# Shift_register.net
KiCad netlist of a schematic drawn in Altium Designer
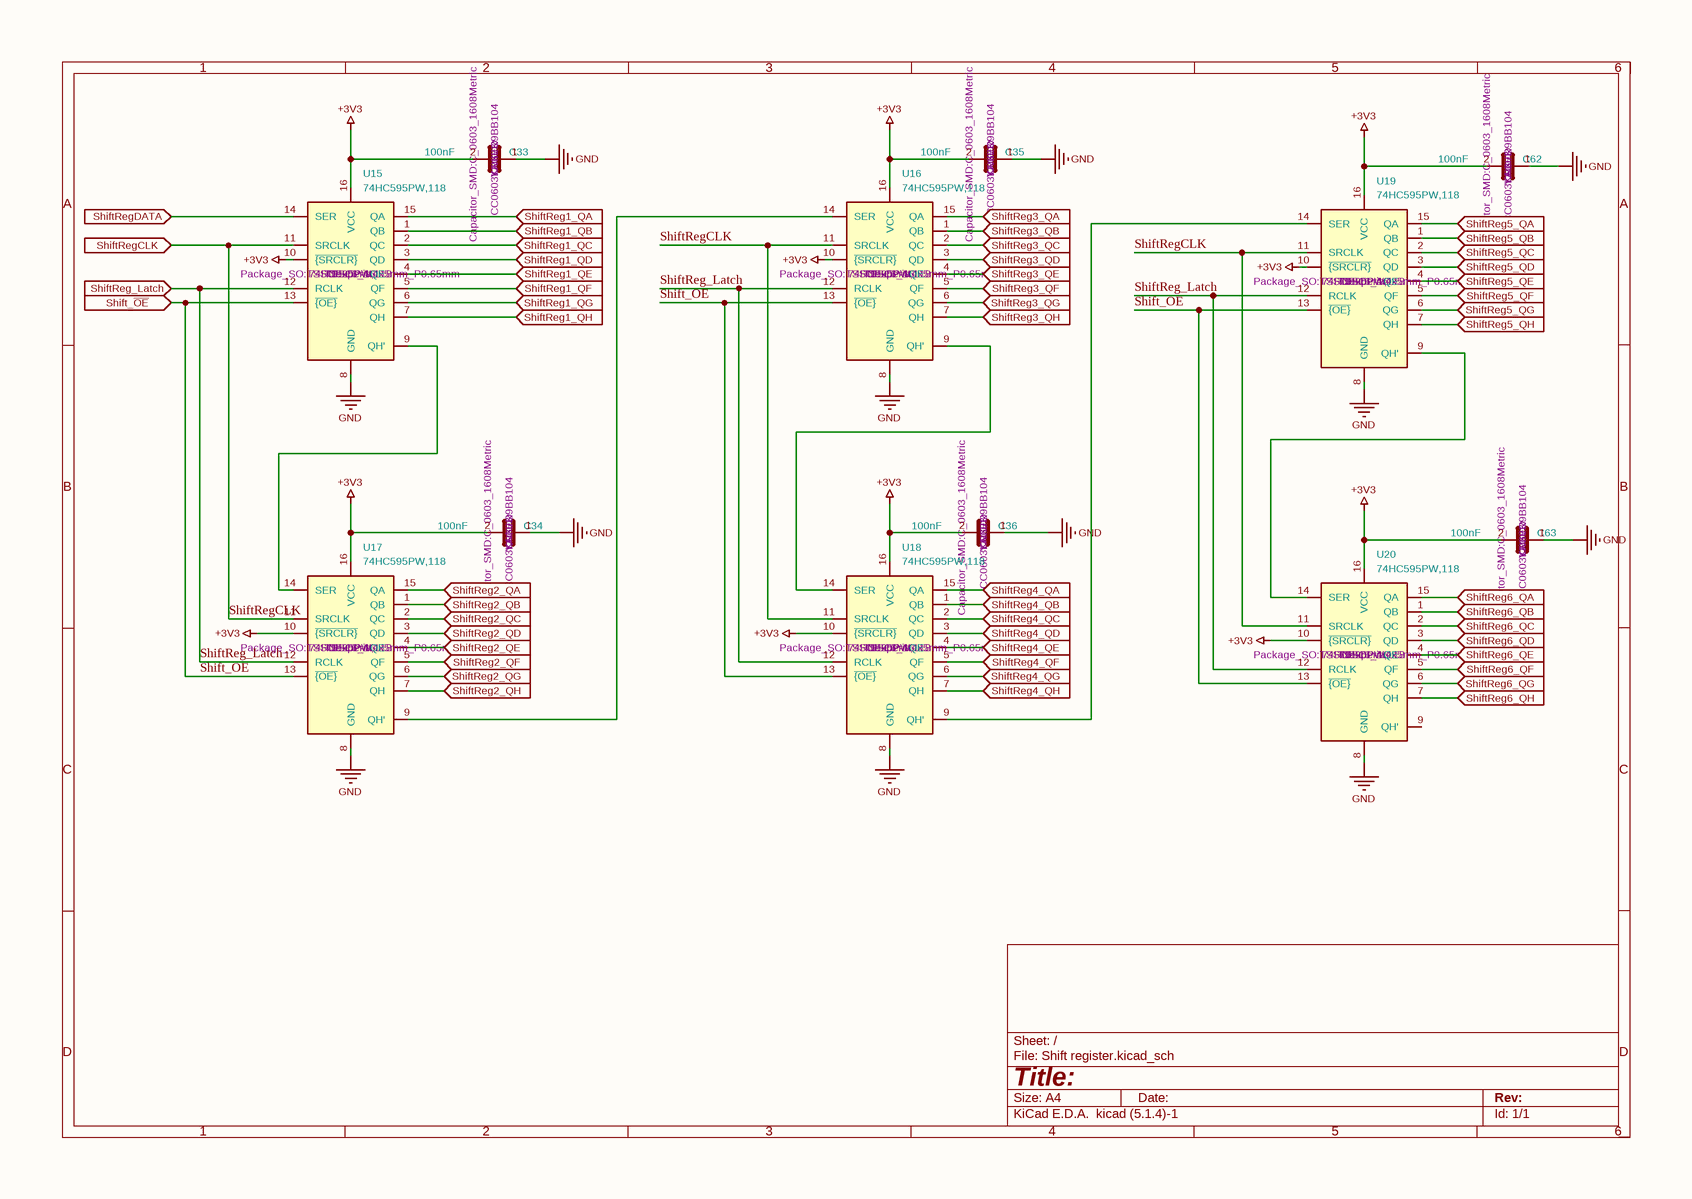
[diagram p0: Shift register.SchDoc]

(export (version "E")
  (design (tool "Eeschema 10.0.6"))
  (components
    (comp (ref "C33")
      (value "100nF")
      (footprint "Capacitor_SMD:C_0603_1608Metric")
      (fields
        (field (name "MANUFACTURER PART NUMBER") "CC0603KRX7R9BB104")
        (field (name "MANUFACTURER") "YAGEO")
        (field (name "PACKAGE") "C0603")
      )
      (libsource (lib "Device") (part "C"))
    )
    (comp (ref "C34")
      (value "100nF")
      (footprint "Capacitor_SMD:C_0603_1608Metric")
      (fields
        (field (name "MANUFACTURER PART NUMBER") "CC0603KRX7R9BB104")
        (field (name "MANUFACTURER") "YAGEO")
        (field (name "PACKAGE") "C0603")
      )
      (libsource (lib "Device") (part "C"))
    )
    (comp (ref "C35")
      (value "100nF")
      (footprint "Capacitor_SMD:C_0603_1608Metric")
      (fields
        (field (name "MANUFACTURER PART NUMBER") "CC0603KRX7R9BB104")
        (field (name "MANUFACTURER") "YAGEO")
        (field (name "PACKAGE") "C0603")
      )
      (libsource (lib "Device") (part "C"))
    )
    (comp (ref "C36")
      (value "100nF")
      (footprint "Capacitor_SMD:C_0603_1608Metric")
      (fields
        (field (name "MANUFACTURER PART NUMBER") "CC0603KRX7R9BB104")
        (field (name "MANUFACTURER") "YAGEO")
        (field (name "PACKAGE") "C0603")
      )
      (libsource (lib "Device") (part "C"))
    )
    (comp (ref "C62")
      (value "100nF")
      (footprint "Capacitor_SMD:C_0603_1608Metric")
      (fields
        (field (name "MANUFACTURER PART NUMBER") "CC0603KRX7R9BB104")
        (field (name "MANUFACTURER") "YAGEO")
        (field (name "PACKAGE") "C0603")
      )
      (libsource (lib "Device") (part "C"))
    )
    (comp (ref "C63")
      (value "100nF")
      (footprint "Capacitor_SMD:C_0603_1608Metric")
      (fields
        (field (name "MANUFACTURER PART NUMBER") "CC0603KRX7R9BB104")
        (field (name "MANUFACTURER") "YAGEO")
        (field (name "PACKAGE") "C0603")
      )
      (libsource (lib "Device") (part "C"))
    )
    (comp (ref "U15")
      (value "74HC595PW,118")
      (footprint "Package_SO:TSSOP-16_4.4x5mm_P0.65mm")
      (fields
        (field (name "MANUFACTURER PART NUMBER") "74HC595PW,118")
        (field (name "MANUFACTURER") "Nexperia")
        (field (name "PACKAGE") "TSSOP-16")
      )
      (libsource (lib "74xx") (part "74HC595"))
    )
    (comp (ref "U16")
      (value "74HC595PW,118")
      (footprint "Package_SO:TSSOP-16_4.4x5mm_P0.65mm")
      (fields
        (field (name "MANUFACTURER PART NUMBER") "74HC595PW,118")
        (field (name "MANUFACTURER") "Nexperia")
        (field (name "PACKAGE") "TSSOP-16")
      )
      (libsource (lib "74xx") (part "74HC595"))
    )
    (comp (ref "U17")
      (value "74HC595PW,118")
      (footprint "Package_SO:TSSOP-16_4.4x5mm_P0.65mm")
      (fields
        (field (name "MANUFACTURER PART NUMBER") "74HC595PW,118")
        (field (name "MANUFACTURER") "Nexperia")
        (field (name "PACKAGE") "TSSOP-16")
      )
      (libsource (lib "74xx") (part "74HC595"))
    )
    (comp (ref "U18")
      (value "74HC595PW,118")
      (footprint "Package_SO:TSSOP-16_4.4x5mm_P0.65mm")
      (fields
        (field (name "MANUFACTURER PART NUMBER") "74HC595PW,118")
        (field (name "MANUFACTURER") "Nexperia")
        (field (name "PACKAGE") "TSSOP-16")
      )
      (libsource (lib "74xx") (part "74HC595"))
    )
    (comp (ref "U19")
      (value "74HC595PW,118")
      (footprint "Package_SO:TSSOP-16_4.4x5mm_P0.65mm")
      (fields
        (field (name "MANUFACTURER PART NUMBER") "74HC595PW,118")
        (field (name "MANUFACTURER") "Nexperia")
        (field (name "PACKAGE") "TSSOP-16")
      )
      (libsource (lib "74xx") (part "74HC595"))
    )
    (comp (ref "U20")
      (value "74HC595PW,118")
      (footprint "Package_SO:TSSOP-16_4.4x5mm_P0.65mm")
      (fields
        (field (name "MANUFACTURER PART NUMBER") "74HC595PW,118")
        (field (name "MANUFACTURER") "Nexperia")
        (field (name "PACKAGE") "TSSOP-16")
      )
      (libsource (lib "74xx") (part "74HC595"))
    )
  )
  (nets
    (net (code "1") (name "+3V3") (class "Default")
      (node (ref "C33") (pin "2") (pinfunction "2_2") (pintype "passive"))
      (node (ref "C34") (pin "2") (pinfunction "2_2") (pintype "passive"))
      (node (ref "C35") (pin "2") (pinfunction "2_2") (pintype "passive"))
      (node (ref "C36") (pin "2") (pinfunction "2_2") (pintype "passive"))
      (node (ref "C62") (pin "2") (pinfunction "2_2") (pintype "passive"))
      (node (ref "C63") (pin "2") (pinfunction "2_2") (pintype "passive"))
      (node (ref "U15") (pin "10") (pinfunction "~{{SRCLR}}_10") (pintype "passive"))
      (node (ref "U15") (pin "16") (pinfunction "VCC_16") (pintype "passive"))
      (node (ref "U16") (pin "10") (pinfunction "~{{SRCLR}}_10") (pintype "passive"))
      (node (ref "U16") (pin "16") (pinfunction "VCC_16") (pintype "passive"))
      (node (ref "U17") (pin "10") (pinfunction "~{{SRCLR}}_10") (pintype "passive"))
      (node (ref "U17") (pin "16") (pinfunction "VCC_16") (pintype "passive"))
      (node (ref "U18") (pin "10") (pinfunction "~{{SRCLR}}_10") (pintype "passive"))
      (node (ref "U18") (pin "16") (pinfunction "VCC_16") (pintype "passive"))
      (node (ref "U19") (pin "10") (pinfunction "~{{SRCLR}}_10") (pintype "passive"))
      (node (ref "U19") (pin "16") (pinfunction "VCC_16") (pintype "passive"))
      (node (ref "U20") (pin "10") (pinfunction "~{{SRCLR}}_10") (pintype "passive"))
      (node (ref "U20") (pin "16") (pinfunction "VCC_16") (pintype "passive"))
    )
    (net (code "2") (name "/ShiftReg1_QA") (class "Default")
      (node (ref "U15") (pin "15") (pinfunction "QA_15") (pintype "passive"))
    )
    (net (code "3") (name "/ShiftReg1_QB") (class "Default")
      (node (ref "U15") (pin "1") (pinfunction "QB_1") (pintype "passive"))
    )
    (net (code "4") (name "/ShiftReg1_QC") (class "Default")
      (node (ref "U15") (pin "2") (pinfunction "QC_2") (pintype "passive"))
    )
    (net (code "5") (name "/ShiftReg1_QD") (class "Default")
      (node (ref "U15") (pin "3") (pinfunction "QD_3") (pintype "passive"))
    )
    (net (code "6") (name "/ShiftReg1_QE") (class "Default")
      (node (ref "U15") (pin "4") (pinfunction "QE_4") (pintype "passive"))
    )
    (net (code "7") (name "/ShiftReg1_QF") (class "Default")
      (node (ref "U15") (pin "5") (pinfunction "QF_5") (pintype "passive"))
    )
    (net (code "8") (name "/ShiftReg1_QG") (class "Default")
      (node (ref "U15") (pin "6") (pinfunction "QG_6") (pintype "passive"))
    )
    (net (code "9") (name "/ShiftReg1_QH") (class "Default")
      (node (ref "U15") (pin "7") (pinfunction "QH_7") (pintype "passive"))
    )
    (net (code "10") (name "/ShiftReg2_QA") (class "Default")
      (node (ref "U17") (pin "15") (pinfunction "QA_15") (pintype "passive"))
    )
    (net (code "11") (name "/ShiftReg2_QB") (class "Default")
      (node (ref "U17") (pin "1") (pinfunction "QB_1") (pintype "passive"))
    )
    (net (code "12") (name "/ShiftReg2_QC") (class "Default")
      (node (ref "U17") (pin "2") (pinfunction "QC_2") (pintype "passive"))
    )
    (net (code "13") (name "/ShiftReg2_QD") (class "Default")
      (node (ref "U17") (pin "3") (pinfunction "QD_3") (pintype "passive"))
    )
    (net (code "14") (name "/ShiftReg2_QE") (class "Default")
      (node (ref "U17") (pin "4") (pinfunction "QE_4") (pintype "passive"))
    )
    (net (code "15") (name "/ShiftReg2_QF") (class "Default")
      (node (ref "U17") (pin "5") (pinfunction "QF_5") (pintype "passive"))
    )
    (net (code "16") (name "/ShiftReg2_QG") (class "Default")
      (node (ref "U17") (pin "6") (pinfunction "QG_6") (pintype "passive"))
    )
    (net (code "17") (name "/ShiftReg2_QH") (class "Default")
      (node (ref "U17") (pin "7") (pinfunction "QH_7") (pintype "passive"))
    )
    (net (code "18") (name "/ShiftReg3_QA") (class "Default")
      (node (ref "U16") (pin "15") (pinfunction "QA_15") (pintype "passive"))
    )
    (net (code "19") (name "/ShiftReg3_QB") (class "Default")
      (node (ref "U16") (pin "1") (pinfunction "QB_1") (pintype "passive"))
    )
    (net (code "20") (name "/ShiftReg3_QC") (class "Default")
      (node (ref "U16") (pin "2") (pinfunction "QC_2") (pintype "passive"))
    )
    (net (code "21") (name "/ShiftReg3_QD") (class "Default")
      (node (ref "U16") (pin "3") (pinfunction "QD_3") (pintype "passive"))
    )
    (net (code "22") (name "/ShiftReg3_QE") (class "Default")
      (node (ref "U16") (pin "4") (pinfunction "QE_4") (pintype "passive"))
    )
    (net (code "23") (name "/ShiftReg3_QF") (class "Default")
      (node (ref "U16") (pin "5") (pinfunction "QF_5") (pintype "passive"))
    )
    (net (code "24") (name "/ShiftReg3_QG") (class "Default")
      (node (ref "U16") (pin "6") (pinfunction "QG_6") (pintype "passive"))
    )
    (net (code "25") (name "/ShiftReg3_QH") (class "Default")
      (node (ref "U16") (pin "7") (pinfunction "QH_7") (pintype "passive"))
    )
    (net (code "26") (name "/ShiftReg4_QA") (class "Default")
      (node (ref "U18") (pin "15") (pinfunction "QA_15") (pintype "passive"))
    )
    (net (code "27") (name "/ShiftReg4_QB") (class "Default")
      (node (ref "U18") (pin "1") (pinfunction "QB_1") (pintype "passive"))
    )
    (net (code "28") (name "/ShiftReg4_QC") (class "Default")
      (node (ref "U18") (pin "2") (pinfunction "QC_2") (pintype "passive"))
    )
    (net (code "29") (name "/ShiftReg4_QD") (class "Default")
      (node (ref "U18") (pin "3") (pinfunction "QD_3") (pintype "passive"))
    )
    (net (code "30") (name "/ShiftReg4_QE") (class "Default")
      (node (ref "U18") (pin "4") (pinfunction "QE_4") (pintype "passive"))
    )
    (net (code "31") (name "/ShiftReg4_QF") (class "Default")
      (node (ref "U18") (pin "5") (pinfunction "QF_5") (pintype "passive"))
    )
    (net (code "32") (name "/ShiftReg4_QG") (class "Default")
      (node (ref "U18") (pin "6") (pinfunction "QG_6") (pintype "passive"))
    )
    (net (code "33") (name "/ShiftReg4_QH") (class "Default")
      (node (ref "U18") (pin "7") (pinfunction "QH_7") (pintype "passive"))
    )
    (net (code "34") (name "/ShiftReg5_QA") (class "Default")
      (node (ref "U19") (pin "15") (pinfunction "QA_15") (pintype "passive"))
    )
    (net (code "35") (name "/ShiftReg5_QB") (class "Default")
      (node (ref "U19") (pin "1") (pinfunction "QB_1") (pintype "passive"))
    )
    (net (code "36") (name "/ShiftReg5_QC") (class "Default")
      (node (ref "U19") (pin "2") (pinfunction "QC_2") (pintype "passive"))
    )
    (net (code "37") (name "/ShiftReg5_QD") (class "Default")
      (node (ref "U19") (pin "3") (pinfunction "QD_3") (pintype "passive"))
    )
    (net (code "38") (name "/ShiftReg5_QE") (class "Default")
      (node (ref "U19") (pin "4") (pinfunction "QE_4") (pintype "passive"))
    )
    (net (code "39") (name "/ShiftReg5_QF") (class "Default")
      (node (ref "U19") (pin "5") (pinfunction "QF_5") (pintype "passive"))
    )
    (net (code "40") (name "/ShiftReg5_QG") (class "Default")
      (node (ref "U19") (pin "6") (pinfunction "QG_6") (pintype "passive"))
    )
    (net (code "41") (name "/ShiftReg5_QH") (class "Default")
      (node (ref "U19") (pin "7") (pinfunction "QH_7") (pintype "passive"))
    )
    (net (code "42") (name "/ShiftReg6_QA") (class "Default")
      (node (ref "U20") (pin "15") (pinfunction "QA_15") (pintype "passive"))
    )
    (net (code "43") (name "/ShiftReg6_QB") (class "Default")
      (node (ref "U20") (pin "1") (pinfunction "QB_1") (pintype "passive"))
    )
    (net (code "44") (name "/ShiftReg6_QC") (class "Default")
      (node (ref "U20") (pin "2") (pinfunction "QC_2") (pintype "passive"))
    )
    (net (code "45") (name "/ShiftReg6_QD") (class "Default")
      (node (ref "U20") (pin "3") (pinfunction "QD_3") (pintype "passive"))
    )
    (net (code "46") (name "/ShiftReg6_QE") (class "Default")
      (node (ref "U20") (pin "4") (pinfunction "QE_4") (pintype "passive"))
    )
    (net (code "47") (name "/ShiftReg6_QF") (class "Default")
      (node (ref "U20") (pin "5") (pinfunction "QF_5") (pintype "passive"))
    )
    (net (code "48") (name "/ShiftReg6_QG") (class "Default")
      (node (ref "U20") (pin "6") (pinfunction "QG_6") (pintype "passive"))
    )
    (net (code "49") (name "/ShiftReg6_QH") (class "Default")
      (node (ref "U20") (pin "7") (pinfunction "QH_7") (pintype "passive"))
    )
    (net (code "50") (name "/ShiftRegCLK") (class "Default")
      (node (ref "U15") (pin "11") (pinfunction "SRCLK_11") (pintype "passive"))
      (node (ref "U16") (pin "11") (pinfunction "SRCLK_11") (pintype "passive"))
      (node (ref "U17") (pin "11") (pinfunction "SRCLK_11") (pintype "passive"))
      (node (ref "U18") (pin "11") (pinfunction "SRCLK_11") (pintype "passive"))
      (node (ref "U19") (pin "11") (pinfunction "SRCLK_11") (pintype "passive"))
      (node (ref "U20") (pin "11") (pinfunction "SRCLK_11") (pintype "passive"))
    )
    (net (code "51") (name "/ShiftRegDATA") (class "Default")
      (node (ref "U15") (pin "14") (pinfunction "SER_14") (pintype "passive"))
    )
    (net (code "52") (name "/ShiftReg_Latch") (class "Default")
      (node (ref "U15") (pin "12") (pinfunction "RCLK_12") (pintype "passive"))
      (node (ref "U16") (pin "12") (pinfunction "RCLK_12") (pintype "passive"))
      (node (ref "U17") (pin "12") (pinfunction "RCLK_12") (pintype "passive"))
      (node (ref "U18") (pin "12") (pinfunction "RCLK_12") (pintype "passive"))
      (node (ref "U19") (pin "12") (pinfunction "RCLK_12") (pintype "passive"))
      (node (ref "U20") (pin "12") (pinfunction "RCLK_12") (pintype "passive"))
    )
    (net (code "53") (name "/Shift_~{OE}") (class "Default")
      (node (ref "U15") (pin "13") (pinfunction "~{{OE}}_13") (pintype "passive"))
      (node (ref "U16") (pin "13") (pinfunction "~{{OE}}_13") (pintype "passive"))
      (node (ref "U17") (pin "13") (pinfunction "~{{OE}}_13") (pintype "passive"))
      (node (ref "U18") (pin "13") (pinfunction "~{{OE}}_13") (pintype "passive"))
      (node (ref "U19") (pin "13") (pinfunction "~{{OE}}_13") (pintype "passive"))
      (node (ref "U20") (pin "13") (pinfunction "~{{OE}}_13") (pintype "passive"))
    )
    (net (code "54") (name "GND") (class "Default")
      (node (ref "C33") (pin "1") (pinfunction "1_1") (pintype "passive"))
      (node (ref "C34") (pin "1") (pinfunction "1_1") (pintype "passive"))
      (node (ref "C35") (pin "1") (pinfunction "1_1") (pintype "passive"))
      (node (ref "C36") (pin "1") (pinfunction "1_1") (pintype "passive"))
      (node (ref "C62") (pin "1") (pinfunction "1_1") (pintype "passive"))
      (node (ref "C63") (pin "1") (pinfunction "1_1") (pintype "passive"))
      (node (ref "U15") (pin "8") (pinfunction "GND_8") (pintype "passive"))
      (node (ref "U16") (pin "8") (pinfunction "GND_8") (pintype "passive"))
      (node (ref "U17") (pin "8") (pinfunction "GND_8") (pintype "passive"))
      (node (ref "U18") (pin "8") (pinfunction "GND_8") (pintype "passive"))
      (node (ref "U19") (pin "8") (pinfunction "GND_8") (pintype "passive"))
      (node (ref "U20") (pin "8") (pinfunction "GND_8") (pintype "passive"))
    )
    (net (code "55") (name "Net-(U15-QH')") (class "Default")
      (node (ref "U15") (pin "9") (pinfunction "QH'_9") (pintype "passive"))
      (node (ref "U17") (pin "14") (pinfunction "SER_14") (pintype "passive"))
    )
    (net (code "56") (name "Net-(U16-QH')") (class "Default")
      (node (ref "U16") (pin "9") (pinfunction "QH'_9") (pintype "passive"))
      (node (ref "U18") (pin "14") (pinfunction "SER_14") (pintype "passive"))
    )
    (net (code "57") (name "Net-(U16-SER)") (class "Default")
      (node (ref "U16") (pin "14") (pinfunction "SER_14") (pintype "passive"))
      (node (ref "U17") (pin "9") (pinfunction "QH'_9") (pintype "passive"))
    )
    (net (code "58") (name "Net-(U18-QH')") (class "Default")
      (node (ref "U18") (pin "9") (pinfunction "QH'_9") (pintype "passive"))
      (node (ref "U19") (pin "14") (pinfunction "SER_14") (pintype "passive"))
    )
    (net (code "59") (name "Net-(U19-QH')") (class "Default")
      (node (ref "U19") (pin "9") (pinfunction "QH'_9") (pintype "passive"))
      (node (ref "U20") (pin "14") (pinfunction "SER_14") (pintype "passive"))
    )
    (net (code "60") (name "unconnected-(U20-QH'-Pad9)") (class "Default")
      (node (ref "U20") (pin "9") (pinfunction "QH'_9") (pintype "passive"))
    )
  )
)
